# cpld_cam.net
KiCad netlist of a schematic drawn in Altium Designer
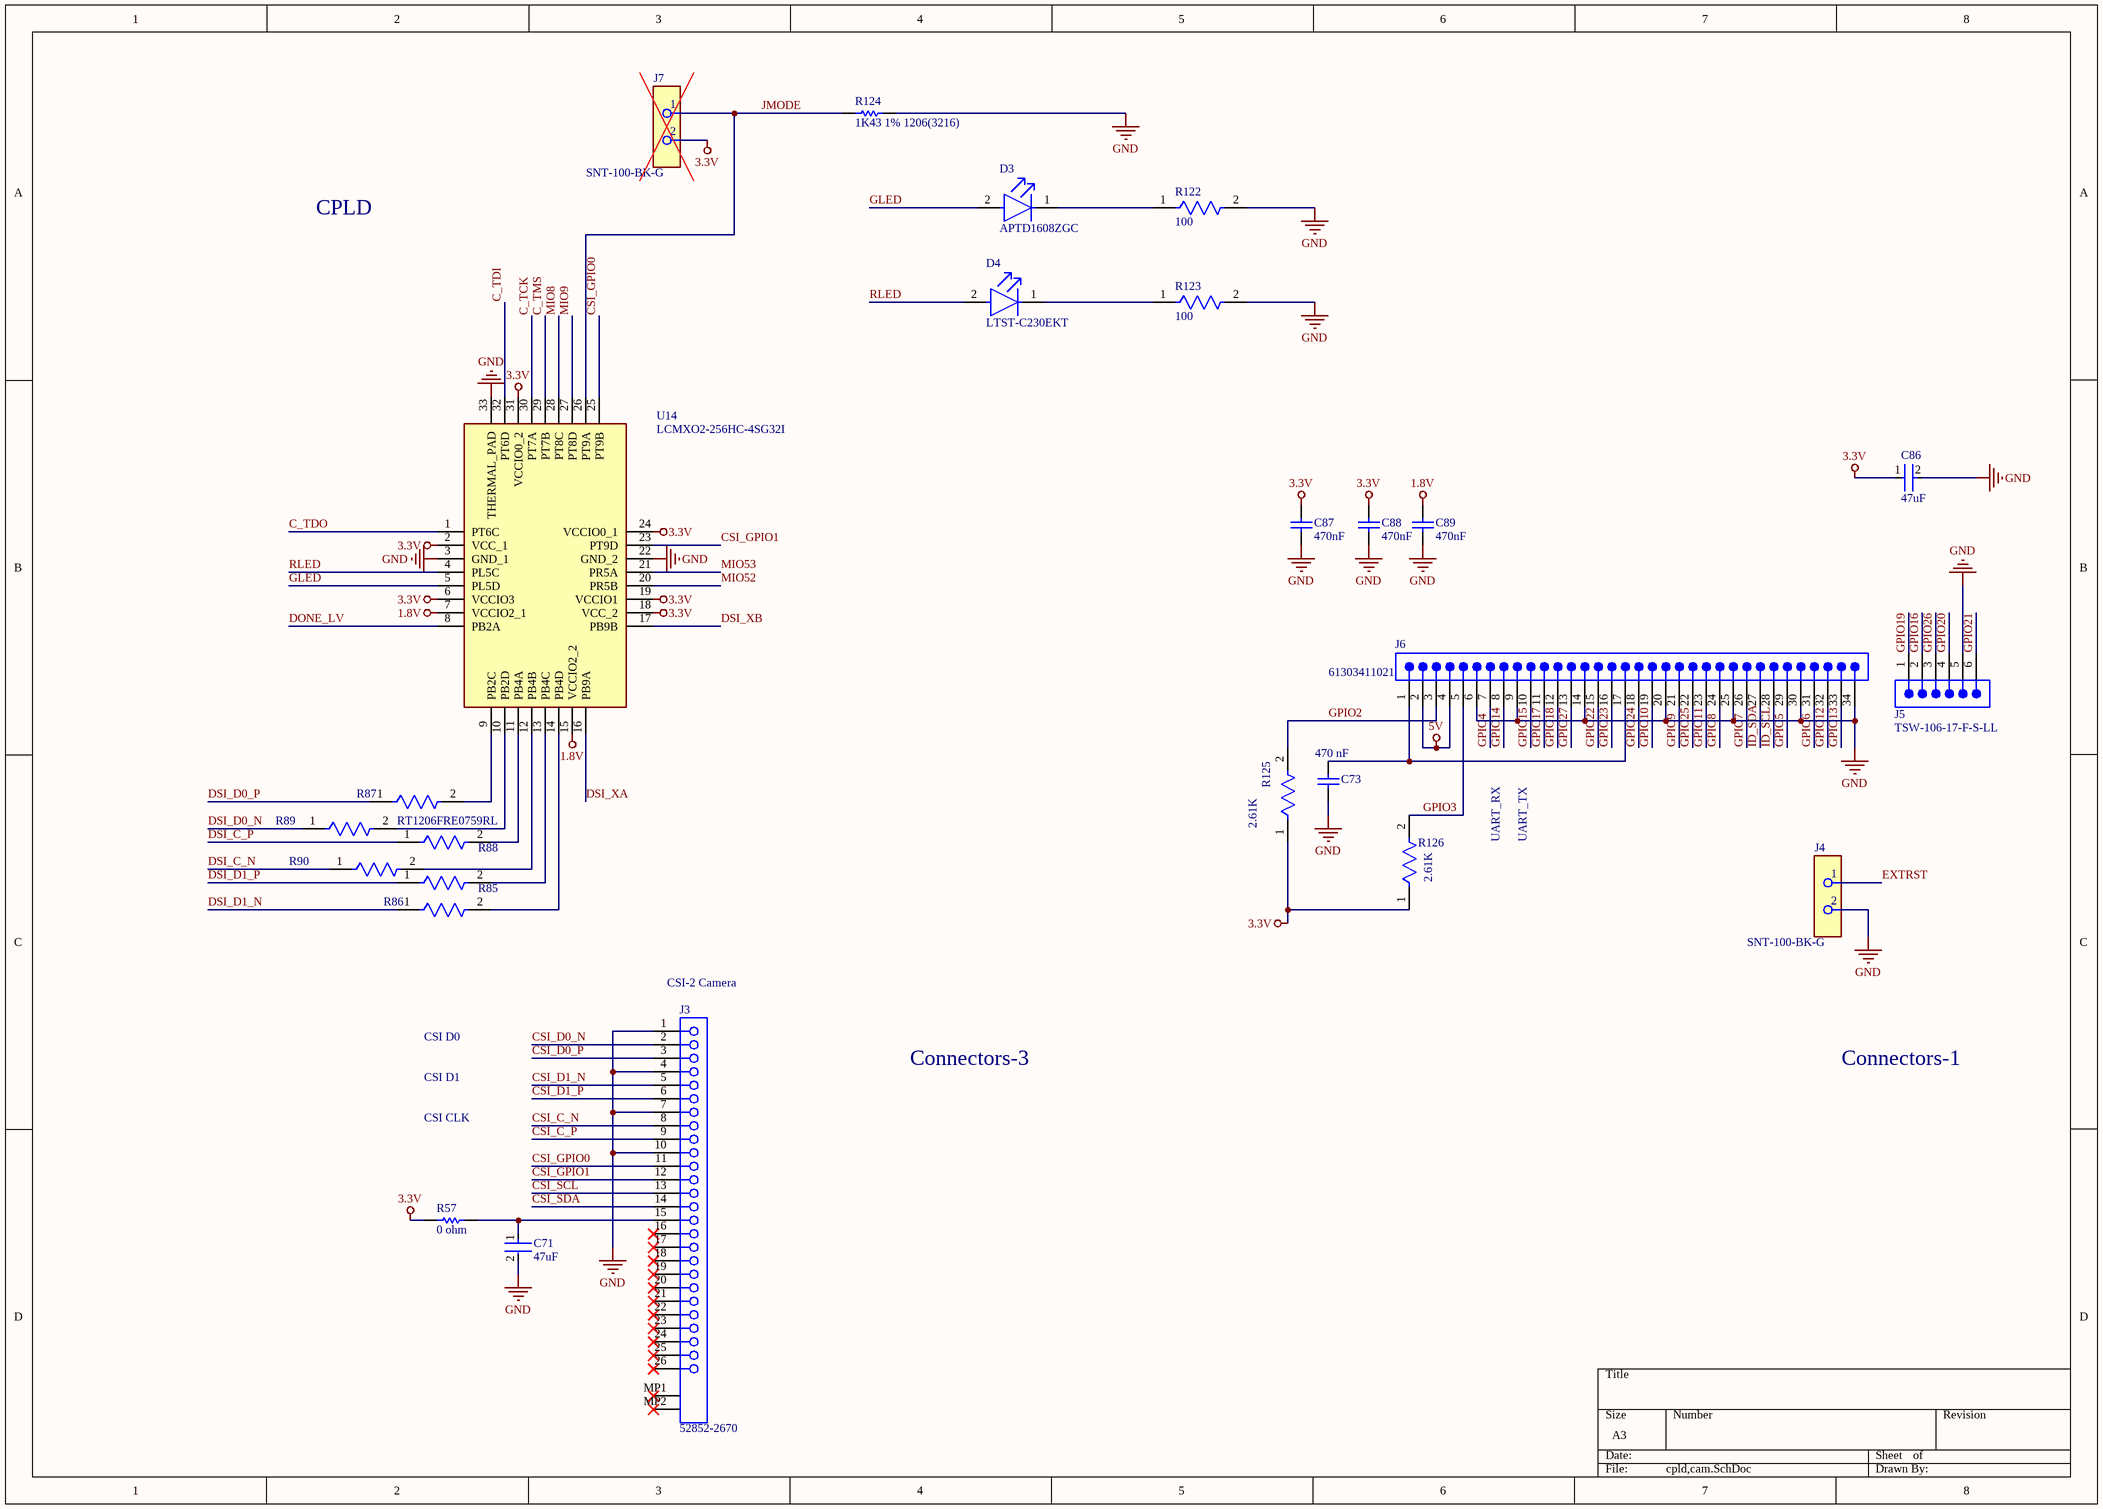
[diagram p0: cpld,cam.SchDoc]

(export (version "E")
  (design (tool "Eeschema 10.0.6"))
  (components
    (comp (ref "C71")
      (value "47uF")
      (footprint "FP-GRM188-0_2-IPC_C")
      (description "Chip Multilayer Ceramic Capacitors for General Purpose, 0603, 47uF, X5R, 15%, 20%, 4V")
      (libsource (lib "Altium Content Vault") (part "11868f565c42a9108669ba33697ecf6"))
    )
    (comp (ref "C73")
      (value "470 nF")
      (footprint "CAPC2013X140X50ML20T25")
      (fields
        (field (name "MANUFACTURER") "AVX Interconnect / Elco")
        (field (name "PART NUMBER") "08055C474JAT2A")
      )
      (libsource (lib "Altium Content Vault") (part "CAP"))
    )
    (comp (ref "C86")
      (value "47uF")
      (footprint "FP-GRM31C-0_3-e0_3_0_8-IPC_C")
      (description "Chip Multilayer Ceramic Capacitors for General Purpose, 1206, 47uF, X5R, 15%, 20%, 16V")
      (fields (field (name "TOLERANCE") "20%"))
      (libsource (lib "Altium Content Vault") (part "f23184f103b6ebe33a8c269c53dcba6"))
    )
    (comp (ref "C87")
      (value "470nF")
      (footprint "CAPC2013X140X50ML20T25")
      (fields
        (field (name "MANUFACTURER") "AVX Interconnect / Elco")
        (field (name "PART NUMBER") "08055C474JAT2A")
      )
      (libsource (lib "Altium Content Vault") (part "CAP"))
    )
    (comp (ref "C88")
      (value "470nF")
      (footprint "CAPC2013X140X50ML20T25")
      (fields
        (field (name "MANUFACTURER") "AVX Interconnect / Elco")
        (field (name "PART NUMBER") "08055C474JAT2A")
      )
      (libsource (lib "Altium Content Vault") (part "CAP"))
    )
    (comp (ref "C89")
      (value "470nF")
      (footprint "CAPC2013X140X50ML20T25")
      (fields
        (field (name "MANUFACTURER") "AVX Interconnect / Elco")
        (field (name "PART NUMBER") "08055C474JAT2A")
      )
      (libsource (lib "Altium Content Vault") (part "CAP"))
    )
    (comp (ref "D3")
      (value "APTD1608ZGC")
      (footprint "FP-APTD1608ZGC-MFG")
      (description "LED GREEN CLEAR CHIP SMD")
      (libsource (lib "Altium Content Vault") (part "8706943c75ba83719d021d2fdc84c58"))
    )
    (comp (ref "D4")
      (value "LTST-C230EKT")
      (footprint "FP-LTST-C230EKT-MFG")
      (description "LED RED CLEAR CHIP SMD")
      (libsource (lib "Altium Content Vault") (part "8706943c75ba83719d021d2fdc84c58"))
    )
    (comp (ref "J3")
      (value "52852-2670")
      (footprint "MOLX-52852-2670")
      (fields (field (name "MANUFACTURER") "Molex"))
      (libsource (lib "Altium Content Vault") (part "MOLX-52852-2670"))
    )
    (comp (ref "J4")
      (value "SNT-100-BK-G")
      (footprint "FP-SNT-100-BK-G-MFG")
      (description "CONN SHUNT 2POS")
      (libsource (lib "Altium Content Vault") (part "245d4dded57b275ea2dfe9722bb6e84"))
    )
    (comp (ref "J5")
      (value "TSW-106-17-F-S-LL")
      (footprint "SMTC-TSW-106-17-X-S-LL")
      (description "0.025\" SQ Post Header, Through-hole, Vertical, -55 to 125 degC, 2.54 mm Pitch, 6-Pin, Male, RoHS")
      (fields (field (name "MANUFACTURER") "Samtec"))
      (libsource (lib "Altium Content Vault") (part "SMTC-TSW-106-X-X-S-X"))
    )
    (comp (ref "J6")
      (value "61303411021")
      (footprint "61303411021")
      (libsource (lib "Altium Content Vault") (part "Header_Male_1R_34P"))
    )
    (comp (ref "J7")
      (value "SNT-100-BK-G")
      (footprint "FP-SNT-100-BK-G-MFG")
      (description "CONN SHUNT 2POS")
      (libsource (lib "Altium Content Vault") (part "245d4dded57b275ea2dfe9722bb6e84"))
    )
    (comp (ref "R57")
      (value "0 ohm")
      (footprint "RESC3225X70X50LL20T20")
      (fields (field (name "MANUFACTURER") "Panasonic") (field (name "PART NUMBER") "ERJ-S140R00U"))
      (libsource (lib "Altium Content Vault") (part "RES"))
    )
    (comp (ref "R85")
      (value "RT1206FRE0759RL")
      (footprint "FP-RT1206-MFG")
      (description "RES SMD 59 OHM 1% 1/4W 1206")
      (fields
        (field (name "OCTOPART") "https://octopart.com/rt1206fre0759rl-yageo-1483639")
        (field (name "MANUFACTURER") "Yageo")
      )
      (libsource (lib "Altium Content Vault") (part "1029c3af85768c4190bb7ad29bc67b5"))
    )
    (comp (ref "R86")
      (value "RT1206FRE0759RL")
      (footprint "FP-RT1206-MFG")
      (description "RES SMD 59 OHM 1% 1/4W 1206")
      (fields
        (field (name "OCTOPART") "https://octopart.com/rt1206fre0759rl-yageo-1483639")
        (field (name "MANUFACTURER") "Yageo")
      )
      (libsource (lib "Altium Content Vault") (part "1029c3af85768c4190bb7ad29bc67b5"))
    )
    (comp (ref "R87")
      (value "RT1206FRE0759RL")
      (footprint "FP-RT1206-MFG")
      (description "RES SMD 59 OHM 1% 1/4W 1206")
      (fields
        (field (name "OCTOPART") "https://octopart.com/rt1206fre0759rl-yageo-1483639")
        (field (name "MANUFACTURER") "Yageo")
      )
      (libsource (lib "Altium Content Vault") (part "1029c3af85768c4190bb7ad29bc67b5"))
    )
    (comp (ref "R88")
      (value "RT1206FRE0759RL")
      (footprint "FP-RT1206-MFG")
      (description "RES SMD 59 OHM 1% 1/4W 1206")
      (fields
        (field (name "OCTOPART") "https://octopart.com/rt1206fre0759rl-yageo-1483639")
        (field (name "MANUFACTURER") "Yageo")
      )
      (libsource (lib "Altium Content Vault") (part "1029c3af85768c4190bb7ad29bc67b5"))
    )
    (comp (ref "R89")
      (value "RT1206FRE0759RL")
      (footprint "FP-RT1206-MFG")
      (description "RES SMD 59 OHM 1% 1/4W 1206")
      (fields
        (field (name "OCTOPART") "https://octopart.com/rt1206fre0759rl-yageo-1483639")
        (field (name "MANUFACTURER") "Yageo")
      )
      (libsource (lib "Altium Content Vault") (part "1029c3af85768c4190bb7ad29bc67b5"))
    )
    (comp (ref "R90")
      (value "RT1206FRE0759RL")
      (footprint "FP-RT1206-MFG")
      (description "RES SMD 59 OHM 1% 1/4W 1206")
      (fields
        (field (name "OCTOPART") "https://octopart.com/rt1206fre0759rl-yageo-1483639")
        (field (name "MANUFACTURER") "Yageo")
      )
      (libsource (lib "Altium Content Vault") (part "1029c3af85768c4190bb7ad29bc67b5"))
    )
    (comp (ref "R122")
      (value "100")
      (footprint "FP-RMCF0805-IPC_A")
      (description "100Ω ±1% 0.125W 0805 Thick Film Chip Resistor AEC-Q200 compliant")
      (fields (field (name "TOLERANCE") "1%"))
      (libsource (lib "Altium Content Vault") (part "1029c3af85768c4190bb7ad29bc67b5"))
    )
    (comp (ref "R123")
      (value "100")
      (footprint "FP-RMCF0805-IPC_A")
      (description "100Ω ±1% 0.125W 0805 Thick Film Chip Resistor AEC-Q200 compliant")
      (fields (field (name "TOLERANCE") "1%"))
      (libsource (lib "Altium Content Vault") (part "1029c3af85768c4190bb7ad29bc67b5"))
    )
    (comp (ref "R124")
      (value "1K43 1% 1206(3216)")
      (footprint "RESC1206(3216)_M")
      (description "1K43 0.25W 1% 1206 (3216 Metric)  SMD")
      (fields (field (name "POWER") "0.25 W") (field (name "TOLERANCE") "1 %"))
      (libsource (lib "Altium Content Vault") (part "RES"))
    )
    (comp (ref "R125")
      (value "2.61K")
      (footprint "FP-RK73H1J-IPC_B")
      (description "2.61kΩ ±0.5% 0.1W Chip Resistor 0603 Thick Film AEC-Q200 Qualified")
      (libsource (lib "Altium Content Vault") (part "1029c3af85768c4190bb7ad29bc67b5"))
    )
    (comp (ref "R126")
      (value "2.61K")
      (footprint "FP-RK73H1J-IPC_B")
      (description "2.61kΩ ±0.5% 0.1W Chip Resistor 0603 Thick Film AEC-Q200 Qualified")
      (libsource (lib "Altium Content Vault") (part "1029c3af85768c4190bb7ad29bc67b5"))
    )
    (comp (ref "U14")
      (value "LCMXO2-256HC-4SG32I")
      (footprint "SamacSys:QFN50P500X500X60-33N")
      (description "Integrated Circuit")
      (fields (field (name "MOUSER PART NUMBER") "842-LCXO2256HC4SG32I"))
      (libsource (lib "*") (part "LCMXO2-256HC-4SG32I"))
    )
  )
  (nets
    (net (code "1") (name "/CSI_C_N") (class "Default")
      (node (ref "J3") (pin "8") (pinfunction "8_8") (pintype "passive"))
    )
    (net (code "2") (name "/CSI_C_P") (class "Default")
      (node (ref "J3") (pin "9") (pinfunction "9_9") (pintype "passive"))
    )
    (net (code "3") (name "/CSI_D0_N") (class "Default")
      (node (ref "J3") (pin "2") (pinfunction "2_2") (pintype "passive"))
    )
    (net (code "4") (name "/CSI_D0_P") (class "Default")
      (node (ref "J3") (pin "3") (pinfunction "3_3") (pintype "passive"))
    )
    (net (code "5") (name "/CSI_D1_N") (class "Default")
      (node (ref "J3") (pin "5") (pinfunction "5_5") (pintype "passive"))
    )
    (net (code "6") (name "/CSI_D1_P") (class "Default")
      (node (ref "J3") (pin "6") (pinfunction "6_6") (pintype "passive"))
    )
    (net (code "7") (name "/CSI_GPIO0") (class "Default")
      (node (ref "J3") (pin "11") (pinfunction "11_11") (pintype "passive"))
      (node (ref "U14") (pin "25") (pinfunction "PT9B_25") (pintype "passive"))
    )
    (net (code "8") (name "/CSI_GPIO1") (class "Default")
      (node (ref "J3") (pin "12") (pinfunction "12_12") (pintype "passive"))
      (node (ref "U14") (pin "23") (pinfunction "PT9D_23") (pintype "passive"))
    )
    (net (code "9") (name "/CSI_SCL") (class "Default")
      (node (ref "J3") (pin "13") (pinfunction "13_13") (pintype "passive"))
    )
    (net (code "10") (name "/CSI_SDA") (class "Default")
      (node (ref "J3") (pin "14") (pinfunction "14_14") (pintype "passive"))
    )
    (net (code "11") (name "/C_TCK") (class "Default")
      (node (ref "U14") (pin "30") (pinfunction "PT7A_30") (pintype "passive"))
    )
    (net (code "12") (name "/C_TDI") (class "Default")
      (node (ref "U14") (pin "32") (pinfunction "PT6D_32") (pintype "passive"))
    )
    (net (code "13") (name "/C_TDO") (class "Default")
      (node (ref "U14") (pin "1") (pinfunction "PT6C_1") (pintype "passive"))
    )
    (net (code "14") (name "/C_TMS") (class "Default")
      (node (ref "U14") (pin "29") (pinfunction "PT7B_29") (pintype "passive"))
    )
    (net (code "15") (name "/DONE_LV") (class "Default")
      (node (ref "U14") (pin "8") (pinfunction "PB2A_8") (pintype "passive"))
    )
    (net (code "16") (name "/DSI_C_N") (class "Default")
      (node (ref "R90") (pin "1") (pinfunction "1_1") (pintype "passive"))
    )
    (net (code "17") (name "/DSI_C_P") (class "Default")
      (node (ref "R88") (pin "1") (pinfunction "1_1") (pintype "passive"))
    )
    (net (code "18") (name "/DSI_D0_N") (class "Default")
      (node (ref "R89") (pin "1") (pinfunction "1_1") (pintype "passive"))
    )
    (net (code "19") (name "/DSI_D0_P") (class "Default")
      (node (ref "R87") (pin "1") (pinfunction "1_1") (pintype "passive"))
    )
    (net (code "20") (name "/DSI_D1_N") (class "Default")
      (node (ref "R86") (pin "1") (pinfunction "1_1") (pintype "passive"))
    )
    (net (code "21") (name "/DSI_D1_P") (class "Default")
      (node (ref "R85") (pin "1") (pinfunction "1_1") (pintype "passive"))
    )
    (net (code "22") (name "/DSI_XA") (class "Default")
      (node (ref "U14") (pin "16") (pinfunction "PB9A_16") (pintype "passive"))
    )
    (net (code "23") (name "/DSI_XB") (class "Default")
      (node (ref "U14") (pin "17") (pinfunction "PB9B_17") (pintype "passive"))
    )
    (net (code "25") (name "/GLED") (class "Default")
      (node (ref "D3") (pin "2") (pinfunction "A_2") (pintype "passive"))
      (node (ref "U14") (pin "5") (pinfunction "PL5D_5") (pintype "passive"))
    )
    (net (code "26") (name "/GPIO2") (class "Default")
      (node (ref "J6") (pin "3") (pinfunction "3_3") (pintype "passive"))
      (node (ref "R125") (pin "2") (pinfunction "2_2") (pintype "passive"))
    )
    (net (code "27") (name "/GPIO3") (class "Default")
      (node (ref "J6") (pin "5") (pinfunction "5_5") (pintype "passive"))
      (node (ref "R126") (pin "2") (pinfunction "2_2") (pintype "passive"))
    )
    (net (code "28") (name "/GPIO4") (class "Default")
      (node (ref "J6") (pin "7") (pinfunction "7_7") (pintype "passive"))
    )
    (net (code "29") (name "/GPIO5") (class "Default")
      (node (ref "J6") (pin "29") (pinfunction "29_29") (pintype "passive"))
    )
    (net (code "30") (name "/GPIO6") (class "Default")
      (node (ref "J6") (pin "31") (pinfunction "31_31") (pintype "passive"))
    )
    (net (code "31") (name "/GPIO7") (class "Default")
      (node (ref "J6") (pin "26") (pinfunction "26_26") (pintype "passive"))
    )
    (net (code "32") (name "/GPIO8") (class "Default")
      (node (ref "J6") (pin "24") (pinfunction "24_24") (pintype "passive"))
    )
    (net (code "33") (name "/GPIO9") (class "Default")
      (node (ref "J6") (pin "21") (pinfunction "21_21") (pintype "passive"))
    )
    (net (code "34") (name "/GPIO10") (class "Default")
      (node (ref "J6") (pin "19") (pinfunction "19_19") (pintype "passive"))
    )
    (net (code "35") (name "/GPIO11") (class "Default")
      (node (ref "J6") (pin "23") (pinfunction "23_23") (pintype "passive"))
    )
    (net (code "36") (name "/GPIO12") (class "Default")
      (node (ref "J6") (pin "32") (pinfunction "32_32") (pintype "passive"))
    )
    (net (code "37") (name "/GPIO13") (class "Default")
      (node (ref "J6") (pin "33") (pinfunction "33_33") (pintype "passive"))
    )
    (net (code "38") (name "/GPIO14") (class "Default")
      (node (ref "J6") (pin "8") (pinfunction "8_8") (pintype "passive"))
    )
    (net (code "39") (name "/GPIO15") (class "Default")
      (node (ref "J6") (pin "10") (pinfunction "10_10") (pintype "passive"))
    )
    (net (code "40") (name "/GPIO16") (class "Default")
      (node (ref "J5") (pin "2") (pinfunction "2_2") (pintype "passive"))
    )
    (net (code "41") (name "/GPIO17") (class "Default")
      (node (ref "J6") (pin "11") (pinfunction "11_11") (pintype "passive"))
    )
    (net (code "42") (name "/GPIO18") (class "Default")
      (node (ref "J6") (pin "12") (pinfunction "12_12") (pintype "passive"))
    )
    (net (code "43") (name "/GPIO19") (class "Default")
      (node (ref "J5") (pin "1") (pinfunction "1_1") (pintype "passive"))
    )
    (net (code "44") (name "/GPIO20") (class "Default")
      (node (ref "J5") (pin "4") (pinfunction "4_4") (pintype "passive"))
    )
    (net (code "45") (name "/GPIO21") (class "Default")
      (node (ref "J5") (pin "6") (pinfunction "6_6") (pintype "passive"))
    )
    (net (code "46") (name "/GPIO22") (class "Default")
      (node (ref "J6") (pin "15") (pinfunction "15_15") (pintype "passive"))
    )
    (net (code "47") (name "/GPIO23") (class "Default")
      (node (ref "J6") (pin "16") (pinfunction "16_16") (pintype "passive"))
    )
    (net (code "48") (name "/GPIO24") (class "Default")
      (node (ref "J6") (pin "18") (pinfunction "18_18") (pintype "passive"))
    )
    (net (code "49") (name "/GPIO25") (class "Default")
      (node (ref "J6") (pin "22") (pinfunction "22_22") (pintype "passive"))
    )
    (net (code "50") (name "/GPIO26") (class "Default")
      (node (ref "J5") (pin "3") (pinfunction "3_3") (pintype "passive"))
    )
    (net (code "51") (name "/GPIO27") (class "Default")
      (node (ref "J6") (pin "13") (pinfunction "13_13") (pintype "passive"))
    )
    (net (code "52") (name "/ID_SCL") (class "Default")
      (node (ref "J6") (pin "28") (pinfunction "28_28") (pintype "passive"))
    )
    (net (code "53") (name "/ID_SDA") (class "Default")
      (node (ref "J6") (pin "27") (pinfunction "27_27") (pintype "passive"))
    )
    (net (code "54") (name "/JMODE") (class "Default")
      (node (ref "R124") (pin "1") (pinfunction "1_1") (pintype "passive"))
      (node (ref "U14") (pin "26") (pinfunction "PT9A_26") (pintype "passive"))
    )
    (net (code "55") (name "/MIO8") (class "Default")
      (node (ref "U14") (pin "28") (pinfunction "PT8C_28") (pintype "passive"))
    )
    (net (code "56") (name "/MIO9") (class "Default")
      (node (ref "U14") (pin "27") (pinfunction "PT8D_27") (pintype "passive"))
    )
    (net (code "57") (name "/MIO52") (class "Default")
      (node (ref "U14") (pin "20") (pinfunction "PR5B_20") (pintype "passive"))
    )
    (net (code "58") (name "/MIO53") (class "Default")
      (node (ref "U14") (pin "21") (pinfunction "PR5A_21") (pintype "passive"))
    )
    (net (code "59") (name "/RLED") (class "Default")
      (node (ref "D4") (pin "2") (pinfunction "A_2") (pintype "passive"))
      (node (ref "U14") (pin "4") (pinfunction "PL5C_4") (pintype "passive"))
    )
    (net (code "60") (name "1.8V") (class "Default")
      (node (ref "C89") (pin "2") (pinfunction "2_2") (pintype "passive"))
      (node (ref "U14") (pin "15") (pinfunction "VCCIO2_2_15") (pintype "passive"))
      (node (ref "U14") (pin "7") (pinfunction "VCCIO2_1_7") (pintype "passive"))
    )
    (net (code "61") (name "3.3V") (class "Default")
      (node (ref "C86") (pin "1") (pinfunction "1_1") (pintype "passive"))
      (node (ref "C87") (pin "2") (pinfunction "2_2") (pintype "passive"))
      (node (ref "C88") (pin "2") (pinfunction "2_2") (pintype "passive"))
      (node (ref "R125") (pin "1") (pinfunction "1_1") (pintype "passive"))
      (node (ref "R126") (pin "1") (pinfunction "1_1") (pintype "passive"))
      (node (ref "R57") (pin "1") (pinfunction "1_1") (pintype "passive"))
      (node (ref "U14") (pin "18") (pinfunction "VCC_2_18") (pintype "passive"))
      (node (ref "U14") (pin "19") (pinfunction "VCCIO1_19") (pintype "passive"))
      (node (ref "U14") (pin "2") (pinfunction "VCC_1_2") (pintype "passive"))
      (node (ref "U14") (pin "24") (pinfunction "VCCIO0_1_24") (pintype "passive"))
      (node (ref "U14") (pin "31") (pinfunction "VCCIO0_2_31") (pintype "passive"))
      (node (ref "U14") (pin "6") (pinfunction "VCCIO3_6") (pintype "passive"))
    )
    (net (code "62") (name "5V") (class "Default")
      (node (ref "J6") (pin "2") (pinfunction "2_2") (pintype "passive"))
      (node (ref "J6") (pin "4") (pinfunction "4_4") (pintype "passive"))
    )
    (net (code "63") (name "GND") (class "Default")
      (node (ref "C71") (pin "2") (pinfunction "2_2") (pintype "passive"))
      (node (ref "C73") (pin "1") (pinfunction "1_1") (pintype "passive"))
      (node (ref "C86") (pin "2") (pinfunction "2_2") (pintype "passive"))
      (node (ref "C87") (pin "1") (pinfunction "1_1") (pintype "passive"))
      (node (ref "C88") (pin "1") (pinfunction "1_1") (pintype "passive"))
      (node (ref "C89") (pin "1") (pinfunction "1_1") (pintype "passive"))
      (node (ref "J3") (pin "1") (pinfunction "1_1") (pintype "passive"))
      (node (ref "J3") (pin "10") (pinfunction "10_10") (pintype "passive"))
      (node (ref "J3") (pin "4") (pinfunction "4_4") (pintype "passive"))
      (node (ref "J3") (pin "7") (pinfunction "7_7") (pintype "passive"))
      (node (ref "J5") (pin "5") (pinfunction "5_5") (pintype "passive"))
      (node (ref "J6") (pin "14") (pinfunction "14_14") (pintype "passive"))
      (node (ref "J6") (pin "20") (pinfunction "20_20") (pintype "passive"))
      (node (ref "J6") (pin "25") (pinfunction "25_25") (pintype "passive"))
      (node (ref "J6") (pin "30") (pinfunction "30_30") (pintype "passive"))
      (node (ref "J6") (pin "34") (pinfunction "34_34") (pintype "passive"))
      (node (ref "J6") (pin "6") (pinfunction "6_6") (pintype "passive"))
      (node (ref "J6") (pin "9") (pinfunction "9_9") (pintype "passive"))
      (node (ref "R122") (pin "2") (pinfunction "2_2") (pintype "passive"))
      (node (ref "R123") (pin "2") (pinfunction "2_2") (pintype "passive"))
      (node (ref "R124") (pin "2") (pinfunction "2_2") (pintype "passive"))
      (node (ref "U14") (pin "22") (pinfunction "GND_2_22") (pintype "passive"))
      (node (ref "U14") (pin "3") (pinfunction "GND_1_3") (pintype "passive"))
      (node (ref "U14") (pin "33") (pinfunction "THERMAL_PAD_33") (pintype "passive"))
    )
    (net (code "64") (name "Net-(C71-Pad1)") (class "Default")
      (node (ref "C71") (pin "1") (pinfunction "1_1") (pintype "passive"))
      (node (ref "J3") (pin "15") (pinfunction "15_15") (pintype "passive"))
      (node (ref "R57") (pin "2") (pinfunction "2_2") (pintype "passive"))
    )
    (net (code "65") (name "Net-(C73-Pad2)") (class "Default")
      (node (ref "C73") (pin "2") (pinfunction "2_2") (pintype "passive"))
      (node (ref "J6") (pin "1") (pinfunction "1_1") (pintype "passive"))
      (node (ref "J6") (pin "17") (pinfunction "17_17") (pintype "passive"))
    )
    (net (code "66") (name "Net-(D3-C)") (class "Default")
      (node (ref "D3") (pin "1") (pinfunction "C_1") (pintype "passive"))
      (node (ref "R122") (pin "1") (pinfunction "1_1") (pintype "passive"))
    )
    (net (code "67") (name "Net-(D4-C)") (class "Default")
      (node (ref "D4") (pin "1") (pinfunction "C_1") (pintype "passive"))
      (node (ref "R123") (pin "1") (pinfunction "1_1") (pintype "passive"))
    )
    (net (code "68") (name "Net-(U14-PB2C)") (class "Default")
      (node (ref "R87") (pin "2") (pinfunction "2_2") (pintype "passive"))
      (node (ref "U14") (pin "9") (pinfunction "PB2C_9") (pintype "passive"))
    )
    (net (code "69") (name "Net-(U14-PB2D)") (class "Default")
      (node (ref "R89") (pin "2") (pinfunction "2_2") (pintype "passive"))
      (node (ref "U14") (pin "10") (pinfunction "PB2D_10") (pintype "passive"))
    )
    (net (code "70") (name "Net-(U14-PB4A)") (class "Default")
      (node (ref "R88") (pin "2") (pinfunction "2_2") (pintype "passive"))
      (node (ref "U14") (pin "11") (pinfunction "PB4A_11") (pintype "passive"))
    )
    (net (code "71") (name "Net-(U14-PB4B)") (class "Default")
      (node (ref "R90") (pin "2") (pinfunction "2_2") (pintype "passive"))
      (node (ref "U14") (pin "12") (pinfunction "PB4B_12") (pintype "passive"))
    )
    (net (code "72") (name "Net-(U14-PB4C)") (class "Default")
      (node (ref "R85") (pin "2") (pinfunction "2_2") (pintype "passive"))
      (node (ref "U14") (pin "13") (pinfunction "PB4C_13") (pintype "passive"))
    )
    (net (code "73") (name "Net-(U14-PB4D)") (class "Default")
      (node (ref "R86") (pin "2") (pinfunction "2_2") (pintype "passive"))
      (node (ref "U14") (pin "14") (pinfunction "PB4D_14") (pintype "passive"))
    )
    (net (code "74") (name "unconnected-(J3-Pad16)") (class "Default")
      (node (ref "J3") (pin "16") (pinfunction "16_16") (pintype "passive+no_connect"))
    )
    (net (code "75") (name "unconnected-(J3-Pad17)") (class "Default")
      (node (ref "J3") (pin "17") (pinfunction "17_17") (pintype "passive+no_connect"))
    )
    (net (code "76") (name "unconnected-(J3-Pad18)") (class "Default")
      (node (ref "J3") (pin "18") (pinfunction "18_18") (pintype "passive+no_connect"))
    )
    (net (code "77") (name "unconnected-(J3-Pad19)") (class "Default")
      (node (ref "J3") (pin "19") (pinfunction "19_19") (pintype "passive+no_connect"))
    )
    (net (code "78") (name "unconnected-(J3-Pad20)") (class "Default")
      (node (ref "J3") (pin "20") (pinfunction "20_20") (pintype "passive+no_connect"))
    )
    (net (code "79") (name "unconnected-(J3-Pad21)") (class "Default")
      (node (ref "J3") (pin "21") (pinfunction "21_21") (pintype "passive+no_connect"))
    )
    (net (code "80") (name "unconnected-(J3-Pad22)") (class "Default")
      (node (ref "J3") (pin "22") (pinfunction "22_22") (pintype "passive+no_connect"))
    )
    (net (code "81") (name "unconnected-(J3-Pad23)") (class "Default")
      (node (ref "J3") (pin "23") (pinfunction "23_23") (pintype "passive+no_connect"))
    )
    (net (code "82") (name "unconnected-(J3-Pad24)") (class "Default")
      (node (ref "J3") (pin "24") (pinfunction "24_24") (pintype "passive+no_connect"))
    )
    (net (code "83") (name "unconnected-(J3-Pad25)") (class "Default")
      (node (ref "J3") (pin "25") (pinfunction "25_25") (pintype "passive+no_connect"))
    )
    (net (code "84") (name "unconnected-(J3-Pad26)") (class "Default")
      (node (ref "J3") (pin "26") (pinfunction "26_26") (pintype "passive+no_connect"))
    )
    (net (code "85") (name "unconnected-(J3-PadMP1)") (class "Default")
      (node (ref "J3") (pin "MP1") (pinfunction "MP1_MP1") (pintype "passive+no_connect"))
    )
    (net (code "86") (name "unconnected-(J3-PadMP2)") (class "Default")
      (node (ref "J3") (pin "MP2") (pinfunction "MP2_MP2") (pintype "passive+no_connect"))
    )
  )
)
